# CONNECTOR.net
KiCad netlist of a schematic drawn in Altium Designer
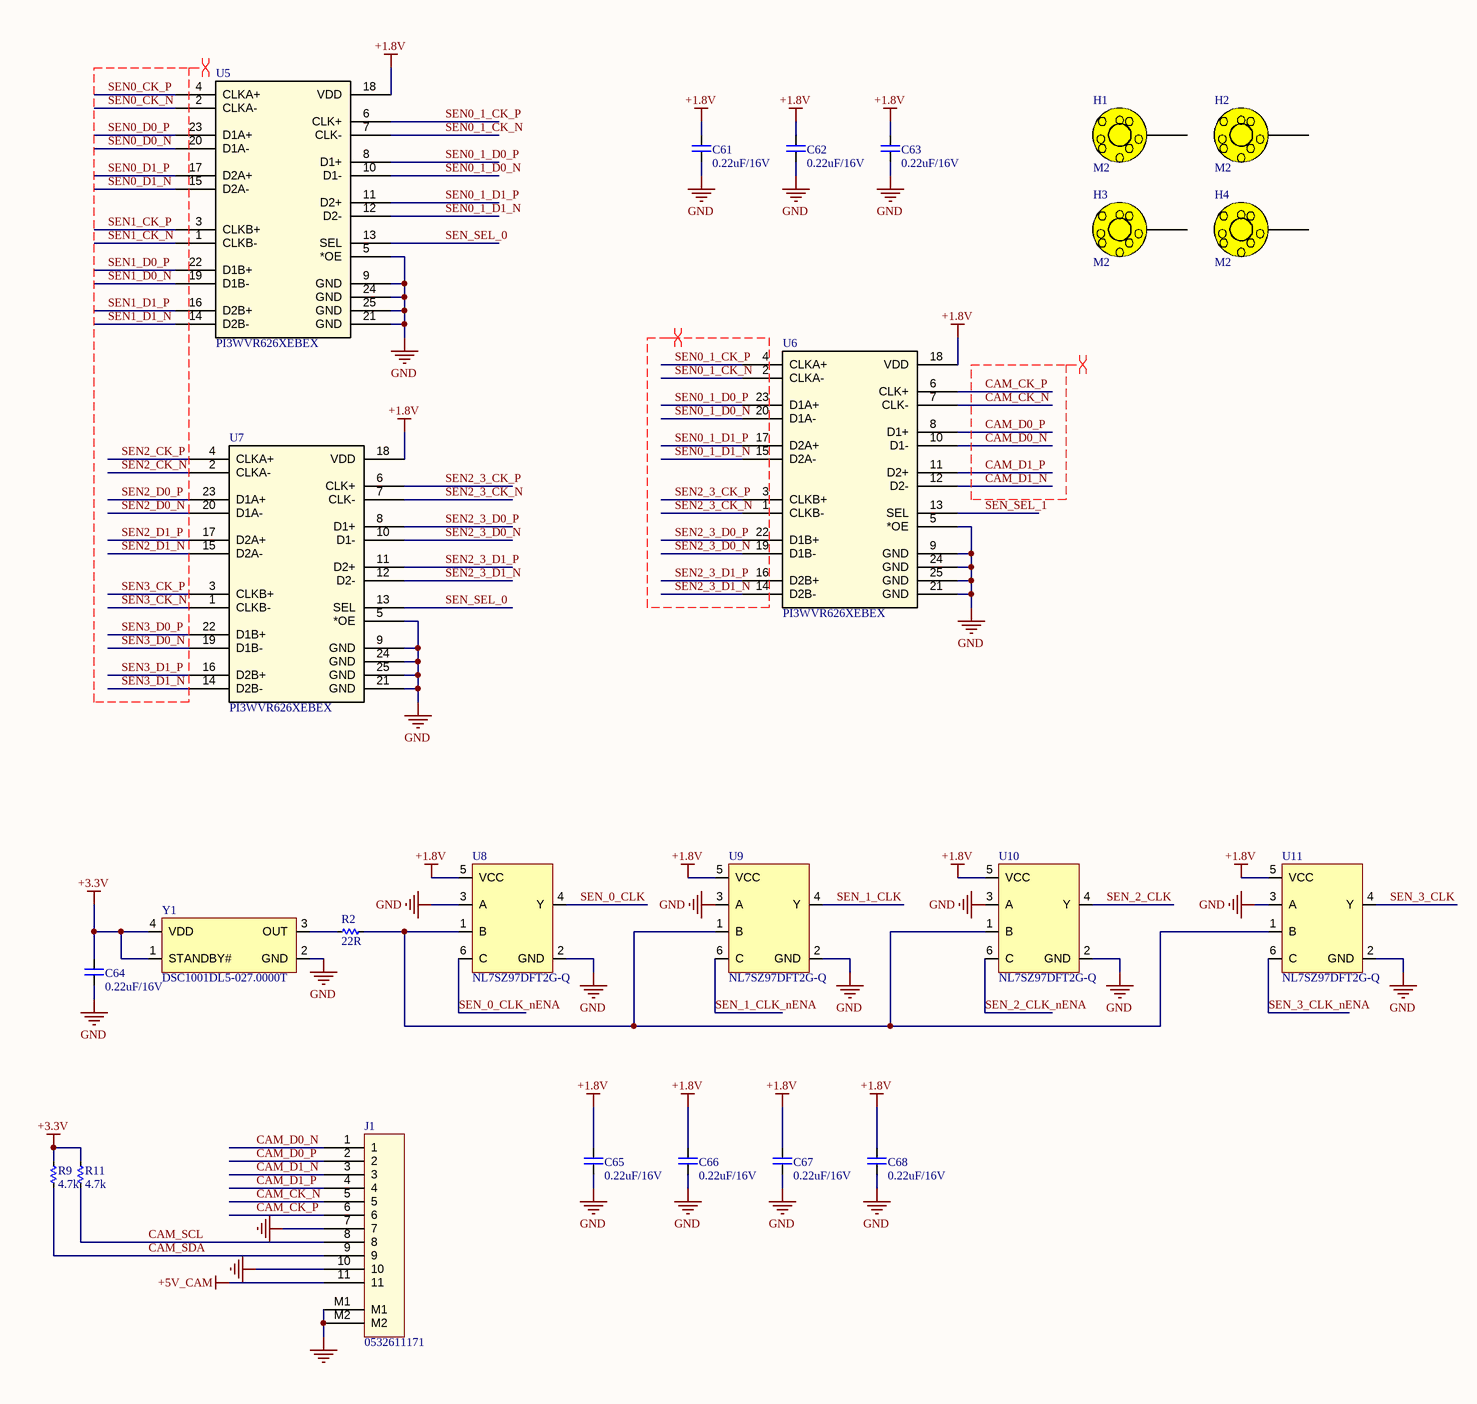
[diagram p0: CONNECTOR.SchDoc]

(export (version "E")
  (design (tool "Eeschema 10.0.6"))
  (components
    (comp (ref "C61")
      (value "0.22uF/16V")
      (footprint "CAP_C_1005X60")
      (description "CAP_Chip")
      (libsource (lib "LABLIB") (part "CAP_SMD"))
    )
    (comp (ref "C62")
      (value "0.22uF/16V")
      (footprint "CAP_C_1005X60")
      (description "CAP_Chip")
      (libsource (lib "LABLIB") (part "CAP_SMD"))
    )
    (comp (ref "C63")
      (value "0.22uF/16V")
      (footprint "CAP_C_1005X60")
      (description "CAP_Chip")
      (libsource (lib "LABLIB") (part "CAP_SMD"))
    )
    (comp (ref "C64")
      (value "0.22uF/16V")
      (footprint "CAP_C_1005X60")
      (description "CAP_Chip")
      (libsource (lib "LABLIB") (part "CAP_SMD"))
    )
    (comp (ref "C65")
      (value "0.22uF/16V")
      (footprint "CAP_C_1005X60")
      (description "CAP_Chip")
      (libsource (lib "LABLIB") (part "CAP_SMD"))
    )
    (comp (ref "C66")
      (value "0.22uF/16V")
      (footprint "CAP_C_1005X60")
      (description "CAP_Chip")
      (libsource (lib "LABLIB") (part "CAP_SMD"))
    )
    (comp (ref "C67")
      (value "0.22uF/16V")
      (footprint "CAP_C_1005X60")
      (description "CAP_Chip")
      (libsource (lib "LABLIB") (part "CAP_SMD"))
    )
    (comp (ref "C68")
      (value "0.22uF/16V")
      (footprint "CAP_C_1005X60")
      (description "CAP_Chip")
      (libsource (lib "LABLIB") (part "CAP_SMD"))
    )
    (comp (ref "H1") (value "M2") (footprint "HEX-2.2mm") (libsource (lib "hex_M3") (part "HEX-M3")))
    (comp (ref "H2") (value "M2") (footprint "HEX-2.2mm") (libsource (lib "hex_M3") (part "HEX-M3")))
    (comp (ref "H3") (value "M2") (footprint "HEX-2.2mm") (libsource (lib "hex_M3") (part "HEX-M3")))
    (comp (ref "H4") (value "M2") (footprint "HEX-2.2mm") (libsource (lib "hex_M3") (part "HEX-M3")))
    (comp (ref "J1")
      (value "0532611171")
      (footprint "MOLEX_0532611171")
      (libsource (lib "LABLIB") (part "Header 11x1_2M"))
    )
    (comp (ref "R2")
      (value "22R")
      (footprint "RES_C_1005X40")
      (description "RES-Chip")
      (fields
        (field (name "MANUFACTURER") "Generic Components")
        (field (name "PUBLISHER") "Altium Hobart Technology Centre")
      )
      (libsource (lib "LABLIB") (part "RES-SMD"))
    )
    (comp (ref "R9")
      (value "4.7k")
      (footprint "RES_C_1005X40")
      (description "RES")
      (libsource (lib "LABLIB") (part "_RES_B_2"))
    )
    (comp (ref "R11")
      (value "4.7k")
      (footprint "RES_C_1005X40")
      (description "RES")
      (libsource (lib "LABLIB") (part "_RES_B_2"))
    )
    (comp (ref "U5")
      (value "PI3WVR626XEBEX")
      (footprint "PI3WVR626XEBEX_DIO_2")
      (libsource (lib "CAMERA_SchLib") (part "PI3WVR626XEBEX"))
    )
    (comp (ref "U6")
      (value "PI3WVR626XEBEX")
      (footprint "PI3WVR626XEBEX_DIO_2")
      (libsource (lib "CAMERA_SchLib") (part "PI3WVR626XEBEX"))
    )
    (comp (ref "U7")
      (value "PI3WVR626XEBEX")
      (footprint "PI3WVR626XEBEX_DIO_2")
      (libsource (lib "CAMERA_SchLib") (part "PI3WVR626XEBEX"))
    )
    (comp (ref "U8")
      (value "NL7SZ97DFT2G-Q")
      (footprint "SC-88")
      (libsource (lib "CAMERA_SchLib") (part "IC_FLEXLOGIC_NL7SZ97DFT2G-Q"))
    )
    (comp (ref "U9")
      (value "NL7SZ97DFT2G-Q")
      (footprint "SC-88")
      (libsource (lib "CAMERA_SchLib") (part "IC_FLEXLOGIC_NL7SZ97DFT2G-Q"))
    )
    (comp (ref "U10")
      (value "NL7SZ97DFT2G-Q")
      (footprint "SC-88")
      (libsource (lib "CAMERA_SchLib") (part "IC_FLEXLOGIC_NL7SZ97DFT2G-Q"))
    )
    (comp (ref "U11")
      (value "NL7SZ97DFT2G-Q")
      (footprint "SC-88")
      (libsource (lib "CAMERA_SchLib") (part "IC_FLEXLOGIC_NL7SZ97DFT2G-Q"))
    )
    (comp (ref "Y1")
      (value "DSC1001DL5-027.0000T")
      (footprint "OSCDFN250X200X89-4N")
      (libsource (lib "CAMERA_SchLib") (part "Y_OSC27MHz_DSC1001DL5-027.0000T"))
    )
  )
  (nets
    (net (code "1") (name "+1.8V") (class "Default")
      (node (ref "C61") (pin "2") (pinfunction "2_2") (pintype "passive"))
      (node (ref "C62") (pin "2") (pinfunction "2_2") (pintype "passive"))
      (node (ref "C63") (pin "2") (pinfunction "2_2") (pintype "passive"))
      (node (ref "C65") (pin "2") (pinfunction "2_2") (pintype "passive"))
      (node (ref "C66") (pin "2") (pinfunction "2_2") (pintype "passive"))
      (node (ref "C67") (pin "2") (pinfunction "2_2") (pintype "passive"))
      (node (ref "C68") (pin "2") (pinfunction "2_2") (pintype "passive"))
      (node (ref "U10") (pin "5") (pinfunction "VCC_5") (pintype "passive"))
      (node (ref "U11") (pin "5") (pinfunction "VCC_5") (pintype "passive"))
      (node (ref "U5") (pin "18") (pinfunction "VDD_18") (pintype "passive"))
      (node (ref "U6") (pin "18") (pinfunction "VDD_18") (pintype "passive"))
      (node (ref "U7") (pin "18") (pinfunction "VDD_18") (pintype "passive"))
      (node (ref "U8") (pin "5") (pinfunction "VCC_5") (pintype "passive"))
      (node (ref "U9") (pin "5") (pinfunction "VCC_5") (pintype "passive"))
    )
    (net (code "2") (name "+3.3V") (class "Default")
      (node (ref "C64") (pin "2") (pinfunction "2_2") (pintype "passive"))
      (node (ref "R11") (pin "1") (pinfunction "1_1") (pintype "passive"))
      (node (ref "R9") (pin "1") (pinfunction "1_1") (pintype "passive"))
      (node (ref "Y1") (pin "1") (pinfunction "STANDBY#_1") (pintype "passive"))
      (node (ref "Y1") (pin "4") (pinfunction "VDD_4") (pintype "passive"))
    )
    (net (code "3") (name "+5V_CAM") (class "Default")
      (node (ref "J1") (pin "11") (pinfunction "11_11") (pintype "passive"))
    )
    (net (code "4") (name "/CAM_CK_N") (class "Default")
      (node (ref "J1") (pin "5") (pinfunction "5_5") (pintype "passive"))
      (node (ref "U6") (pin "7") (pinfunction "CLK-_7") (pintype "passive"))
    )
    (net (code "5") (name "/CAM_CK_P") (class "Default")
      (node (ref "J1") (pin "6") (pinfunction "6_6") (pintype "passive"))
      (node (ref "U6") (pin "6") (pinfunction "CLK+_6") (pintype "passive"))
    )
    (net (code "6") (name "/CAM_D0_N") (class "Default")
      (node (ref "J1") (pin "1") (pinfunction "1_1") (pintype "passive"))
      (node (ref "U6") (pin "10") (pinfunction "D1-_10") (pintype "passive"))
    )
    (net (code "7") (name "/CAM_D0_P") (class "Default")
      (node (ref "J1") (pin "2") (pinfunction "2_2") (pintype "passive"))
      (node (ref "U6") (pin "8") (pinfunction "D1+_8") (pintype "passive"))
    )
    (net (code "8") (name "/CAM_D1_N") (class "Default")
      (node (ref "J1") (pin "3") (pinfunction "3_3") (pintype "passive"))
      (node (ref "U6") (pin "12") (pinfunction "D2-_12") (pintype "passive"))
    )
    (net (code "9") (name "/CAM_D1_P") (class "Default")
      (node (ref "J1") (pin "4") (pinfunction "4_4") (pintype "passive"))
      (node (ref "U6") (pin "11") (pinfunction "D2+_11") (pintype "passive"))
    )
    (net (code "10") (name "/CAM_SCL") (class "Default")
      (node (ref "J1") (pin "8") (pinfunction "8_8") (pintype "passive"))
      (node (ref "R11") (pin "2") (pinfunction "2_2") (pintype "passive"))
    )
    (net (code "11") (name "/CAM_SDA") (class "Default")
      (node (ref "J1") (pin "9") (pinfunction "9_9") (pintype "passive"))
      (node (ref "R9") (pin "2") (pinfunction "2_2") (pintype "passive"))
    )
    (net (code "12") (name "/SEN0_1_CK_N") (class "Default")
      (node (ref "U5") (pin "7") (pinfunction "CLK-_7") (pintype "passive"))
      (node (ref "U6") (pin "2") (pinfunction "CLKA-_2") (pintype "passive"))
    )
    (net (code "13") (name "/SEN0_1_CK_P") (class "Default")
      (node (ref "U5") (pin "6") (pinfunction "CLK+_6") (pintype "passive"))
      (node (ref "U6") (pin "4") (pinfunction "CLKA+_4") (pintype "passive"))
    )
    (net (code "14") (name "/SEN0_1_D0_N") (class "Default")
      (node (ref "U5") (pin "10") (pinfunction "D1-_10") (pintype "passive"))
      (node (ref "U6") (pin "20") (pinfunction "D1A-_20") (pintype "passive"))
    )
    (net (code "15") (name "/SEN0_1_D0_P") (class "Default")
      (node (ref "U5") (pin "8") (pinfunction "D1+_8") (pintype "passive"))
      (node (ref "U6") (pin "23") (pinfunction "D1A+_23") (pintype "passive"))
    )
    (net (code "16") (name "/SEN0_1_D1_N") (class "Default")
      (node (ref "U5") (pin "12") (pinfunction "D2-_12") (pintype "passive"))
      (node (ref "U6") (pin "15") (pinfunction "D2A-_15") (pintype "passive"))
    )
    (net (code "17") (name "/SEN0_1_D1_P") (class "Default")
      (node (ref "U5") (pin "11") (pinfunction "D2+_11") (pintype "passive"))
      (node (ref "U6") (pin "17") (pinfunction "D2A+_17") (pintype "passive"))
    )
    (net (code "18") (name "/SEN0_CK_N") (class "Default")
      (node (ref "U5") (pin "2") (pinfunction "CLKA-_2") (pintype "passive"))
    )
    (net (code "19") (name "/SEN0_CK_P") (class "Default")
      (node (ref "U5") (pin "4") (pinfunction "CLKA+_4") (pintype "passive"))
    )
    (net (code "20") (name "/SEN0_D0_N") (class "Default")
      (node (ref "U5") (pin "20") (pinfunction "D1A-_20") (pintype "passive"))
    )
    (net (code "21") (name "/SEN0_D0_P") (class "Default")
      (node (ref "U5") (pin "23") (pinfunction "D1A+_23") (pintype "passive"))
    )
    (net (code "22") (name "/SEN0_D1_N") (class "Default")
      (node (ref "U5") (pin "15") (pinfunction "D2A-_15") (pintype "passive"))
    )
    (net (code "23") (name "/SEN0_D1_P") (class "Default")
      (node (ref "U5") (pin "17") (pinfunction "D2A+_17") (pintype "passive"))
    )
    (net (code "24") (name "/SEN1_CK_N") (class "Default")
      (node (ref "U5") (pin "1") (pinfunction "CLKB-_1") (pintype "passive"))
    )
    (net (code "25") (name "/SEN1_CK_P") (class "Default")
      (node (ref "U5") (pin "3") (pinfunction "CLKB+_3") (pintype "passive"))
    )
    (net (code "26") (name "/SEN1_D0_N") (class "Default")
      (node (ref "U5") (pin "19") (pinfunction "D1B-_19") (pintype "passive"))
    )
    (net (code "27") (name "/SEN1_D0_P") (class "Default")
      (node (ref "U5") (pin "22") (pinfunction "D1B+_22") (pintype "passive"))
    )
    (net (code "28") (name "/SEN1_D1_N") (class "Default")
      (node (ref "U5") (pin "14") (pinfunction "D2B-_14") (pintype "passive"))
    )
    (net (code "29") (name "/SEN1_D1_P") (class "Default")
      (node (ref "U5") (pin "16") (pinfunction "D2B+_16") (pintype "passive"))
    )
    (net (code "30") (name "/SEN2_3_CK_N") (class "Default")
      (node (ref "U6") (pin "1") (pinfunction "CLKB-_1") (pintype "passive"))
      (node (ref "U7") (pin "7") (pinfunction "CLK-_7") (pintype "passive"))
    )
    (net (code "31") (name "/SEN2_3_CK_P") (class "Default")
      (node (ref "U6") (pin "3") (pinfunction "CLKB+_3") (pintype "passive"))
      (node (ref "U7") (pin "6") (pinfunction "CLK+_6") (pintype "passive"))
    )
    (net (code "32") (name "/SEN2_3_D0_N") (class "Default")
      (node (ref "U6") (pin "19") (pinfunction "D1B-_19") (pintype "passive"))
      (node (ref "U7") (pin "10") (pinfunction "D1-_10") (pintype "passive"))
    )
    (net (code "33") (name "/SEN2_3_D0_P") (class "Default")
      (node (ref "U6") (pin "22") (pinfunction "D1B+_22") (pintype "passive"))
      (node (ref "U7") (pin "8") (pinfunction "D1+_8") (pintype "passive"))
    )
    (net (code "34") (name "/SEN2_3_D1_N") (class "Default")
      (node (ref "U6") (pin "14") (pinfunction "D2B-_14") (pintype "passive"))
      (node (ref "U7") (pin "12") (pinfunction "D2-_12") (pintype "passive"))
    )
    (net (code "35") (name "/SEN2_3_D1_P") (class "Default")
      (node (ref "U6") (pin "16") (pinfunction "D2B+_16") (pintype "passive"))
      (node (ref "U7") (pin "11") (pinfunction "D2+_11") (pintype "passive"))
    )
    (net (code "36") (name "/SEN2_CK_N") (class "Default")
      (node (ref "U7") (pin "2") (pinfunction "CLKA-_2") (pintype "passive"))
    )
    (net (code "37") (name "/SEN2_CK_P") (class "Default")
      (node (ref "U7") (pin "4") (pinfunction "CLKA+_4") (pintype "passive"))
    )
    (net (code "38") (name "/SEN2_D0_N") (class "Default")
      (node (ref "U7") (pin "20") (pinfunction "D1A-_20") (pintype "passive"))
    )
    (net (code "39") (name "/SEN2_D0_P") (class "Default")
      (node (ref "U7") (pin "23") (pinfunction "D1A+_23") (pintype "passive"))
    )
    (net (code "40") (name "/SEN2_D1_N") (class "Default")
      (node (ref "U7") (pin "15") (pinfunction "D2A-_15") (pintype "passive"))
    )
    (net (code "41") (name "/SEN2_D1_P") (class "Default")
      (node (ref "U7") (pin "17") (pinfunction "D2A+_17") (pintype "passive"))
    )
    (net (code "42") (name "/SEN3_CK_N") (class "Default")
      (node (ref "U7") (pin "1") (pinfunction "CLKB-_1") (pintype "passive"))
    )
    (net (code "43") (name "/SEN3_CK_P") (class "Default")
      (node (ref "U7") (pin "3") (pinfunction "CLKB+_3") (pintype "passive"))
    )
    (net (code "44") (name "/SEN3_D0_N") (class "Default")
      (node (ref "U7") (pin "19") (pinfunction "D1B-_19") (pintype "passive"))
    )
    (net (code "45") (name "/SEN3_D0_P") (class "Default")
      (node (ref "U7") (pin "22") (pinfunction "D1B+_22") (pintype "passive"))
    )
    (net (code "46") (name "/SEN3_D1_N") (class "Default")
      (node (ref "U7") (pin "14") (pinfunction "D2B-_14") (pintype "passive"))
    )
    (net (code "47") (name "/SEN3_D1_P") (class "Default")
      (node (ref "U7") (pin "16") (pinfunction "D2B+_16") (pintype "passive"))
    )
    (net (code "48") (name "/SEN_0_CLK") (class "Default")
      (node (ref "U8") (pin "4") (pinfunction "Y_4") (pintype "passive"))
    )
    (net (code "49") (name "/SEN_0_CLK_nENA") (class "Default")
      (node (ref "U8") (pin "6") (pinfunction "C_6") (pintype "passive"))
    )
    (net (code "50") (name "/SEN_1_CLK") (class "Default")
      (node (ref "U9") (pin "4") (pinfunction "Y_4") (pintype "passive"))
    )
    (net (code "51") (name "/SEN_1_CLK_nENA") (class "Default")
      (node (ref "U9") (pin "6") (pinfunction "C_6") (pintype "passive"))
    )
    (net (code "52") (name "/SEN_2_CLK") (class "Default")
      (node (ref "U10") (pin "4") (pinfunction "Y_4") (pintype "passive"))
    )
    (net (code "53") (name "/SEN_2_CLK_nENA") (class "Default")
      (node (ref "U10") (pin "6") (pinfunction "C_6") (pintype "passive"))
    )
    (net (code "54") (name "/SEN_3_CLK") (class "Default")
      (node (ref "U11") (pin "4") (pinfunction "Y_4") (pintype "passive"))
    )
    (net (code "55") (name "/SEN_3_CLK_nENA") (class "Default")
      (node (ref "U11") (pin "6") (pinfunction "C_6") (pintype "passive"))
    )
    (net (code "56") (name "/SEN_SEL_0") (class "Default")
      (node (ref "U5") (pin "13") (pinfunction "SEL_13") (pintype "passive"))
      (node (ref "U7") (pin "13") (pinfunction "SEL_13") (pintype "passive"))
    )
    (net (code "57") (name "/SEN_SEL_1") (class "Default")
      (node (ref "U6") (pin "13") (pinfunction "SEL_13") (pintype "passive"))
    )
    (net (code "58") (name "GND") (class "Default")
      (node (ref "C61") (pin "1") (pinfunction "1_1") (pintype "passive"))
      (node (ref "C62") (pin "1") (pinfunction "1_1") (pintype "passive"))
      (node (ref "C63") (pin "1") (pinfunction "1_1") (pintype "passive"))
      (node (ref "C64") (pin "1") (pinfunction "1_1") (pintype "passive"))
      (node (ref "C65") (pin "1") (pinfunction "1_1") (pintype "passive"))
      (node (ref "C66") (pin "1") (pinfunction "1_1") (pintype "passive"))
      (node (ref "C67") (pin "1") (pinfunction "1_1") (pintype "passive"))
      (node (ref "C68") (pin "1") (pinfunction "1_1") (pintype "passive"))
      (node (ref "J1") (pin "10") (pinfunction "10_10") (pintype "passive"))
      (node (ref "J1") (pin "7") (pinfunction "7_7") (pintype "passive"))
      (node (ref "J1") (pin "M1") (pinfunction "M1_M1") (pintype "passive"))
      (node (ref "J1") (pin "M2") (pinfunction "M2_M2") (pintype "passive"))
      (node (ref "U10") (pin "2") (pinfunction "GND_2") (pintype "passive"))
      (node (ref "U10") (pin "3") (pinfunction "A_3") (pintype "passive"))
      (node (ref "U11") (pin "2") (pinfunction "GND_2") (pintype "passive"))
      (node (ref "U11") (pin "3") (pinfunction "A_3") (pintype "passive"))
      (node (ref "U5") (pin "21") (pinfunction "GND_21") (pintype "passive"))
      (node (ref "U5") (pin "24") (pinfunction "GND_24") (pintype "passive"))
      (node (ref "U5") (pin "25") (pinfunction "GND_25") (pintype "passive"))
      (node (ref "U5") (pin "5") (pinfunction "*OE_5") (pintype "passive"))
      (node (ref "U5") (pin "9") (pinfunction "GND_9") (pintype "passive"))
      (node (ref "U6") (pin "21") (pinfunction "GND_21") (pintype "passive"))
      (node (ref "U6") (pin "24") (pinfunction "GND_24") (pintype "passive"))
      (node (ref "U6") (pin "25") (pinfunction "GND_25") (pintype "passive"))
      (node (ref "U6") (pin "5") (pinfunction "*OE_5") (pintype "passive"))
      (node (ref "U6") (pin "9") (pinfunction "GND_9") (pintype "passive"))
      (node (ref "U7") (pin "21") (pinfunction "GND_21") (pintype "passive"))
      (node (ref "U7") (pin "24") (pinfunction "GND_24") (pintype "passive"))
      (node (ref "U7") (pin "25") (pinfunction "GND_25") (pintype "passive"))
      (node (ref "U7") (pin "5") (pinfunction "*OE_5") (pintype "passive"))
      (node (ref "U7") (pin "9") (pinfunction "GND_9") (pintype "passive"))
      (node (ref "U8") (pin "2") (pinfunction "GND_2") (pintype "passive"))
      (node (ref "U8") (pin "3") (pinfunction "A_3") (pintype "passive"))
      (node (ref "U9") (pin "2") (pinfunction "GND_2") (pintype "passive"))
      (node (ref "U9") (pin "3") (pinfunction "A_3") (pintype "passive"))
      (node (ref "Y1") (pin "2") (pinfunction "GND_2") (pintype "passive"))
    )
    (net (code "59") (name "Net-(U10-B)") (class "Default")
      (node (ref "R2") (pin "1") (pinfunction "1_1") (pintype "passive"))
      (node (ref "U10") (pin "1") (pinfunction "B_1") (pintype "passive"))
      (node (ref "U11") (pin "1") (pinfunction "B_1") (pintype "passive"))
      (node (ref "U8") (pin "1") (pinfunction "B_1") (pintype "passive"))
      (node (ref "U9") (pin "1") (pinfunction "B_1") (pintype "passive"))
    )
    (net (code "60") (name "Net-(Y1-OUT)") (class "Default")
      (node (ref "R2") (pin "2") (pinfunction "2_2") (pintype "passive"))
      (node (ref "Y1") (pin "3") (pinfunction "OUT_3") (pintype "passive"))
    )
    (net (code "61") (name "unconnected-(H1-Pad1)") (class "Default")
      (node (ref "H1") (pin "1") (pinfunction "1_1") (pintype "power_in"))
    )
    (net (code "62") (name "unconnected-(H2-Pad1)") (class "Default")
      (node (ref "H2") (pin "1") (pinfunction "1_1") (pintype "power_in"))
    )
    (net (code "63") (name "unconnected-(H3-Pad1)") (class "Default")
      (node (ref "H3") (pin "1") (pinfunction "1_1") (pintype "power_in"))
    )
    (net (code "64") (name "unconnected-(H4-Pad1)") (class "Default")
      (node (ref "H4") (pin "1") (pinfunction "1_1") (pintype "power_in"))
    )
  )
)
